# PSU.net
KiCad netlist of a schematic drawn in Altium Designer
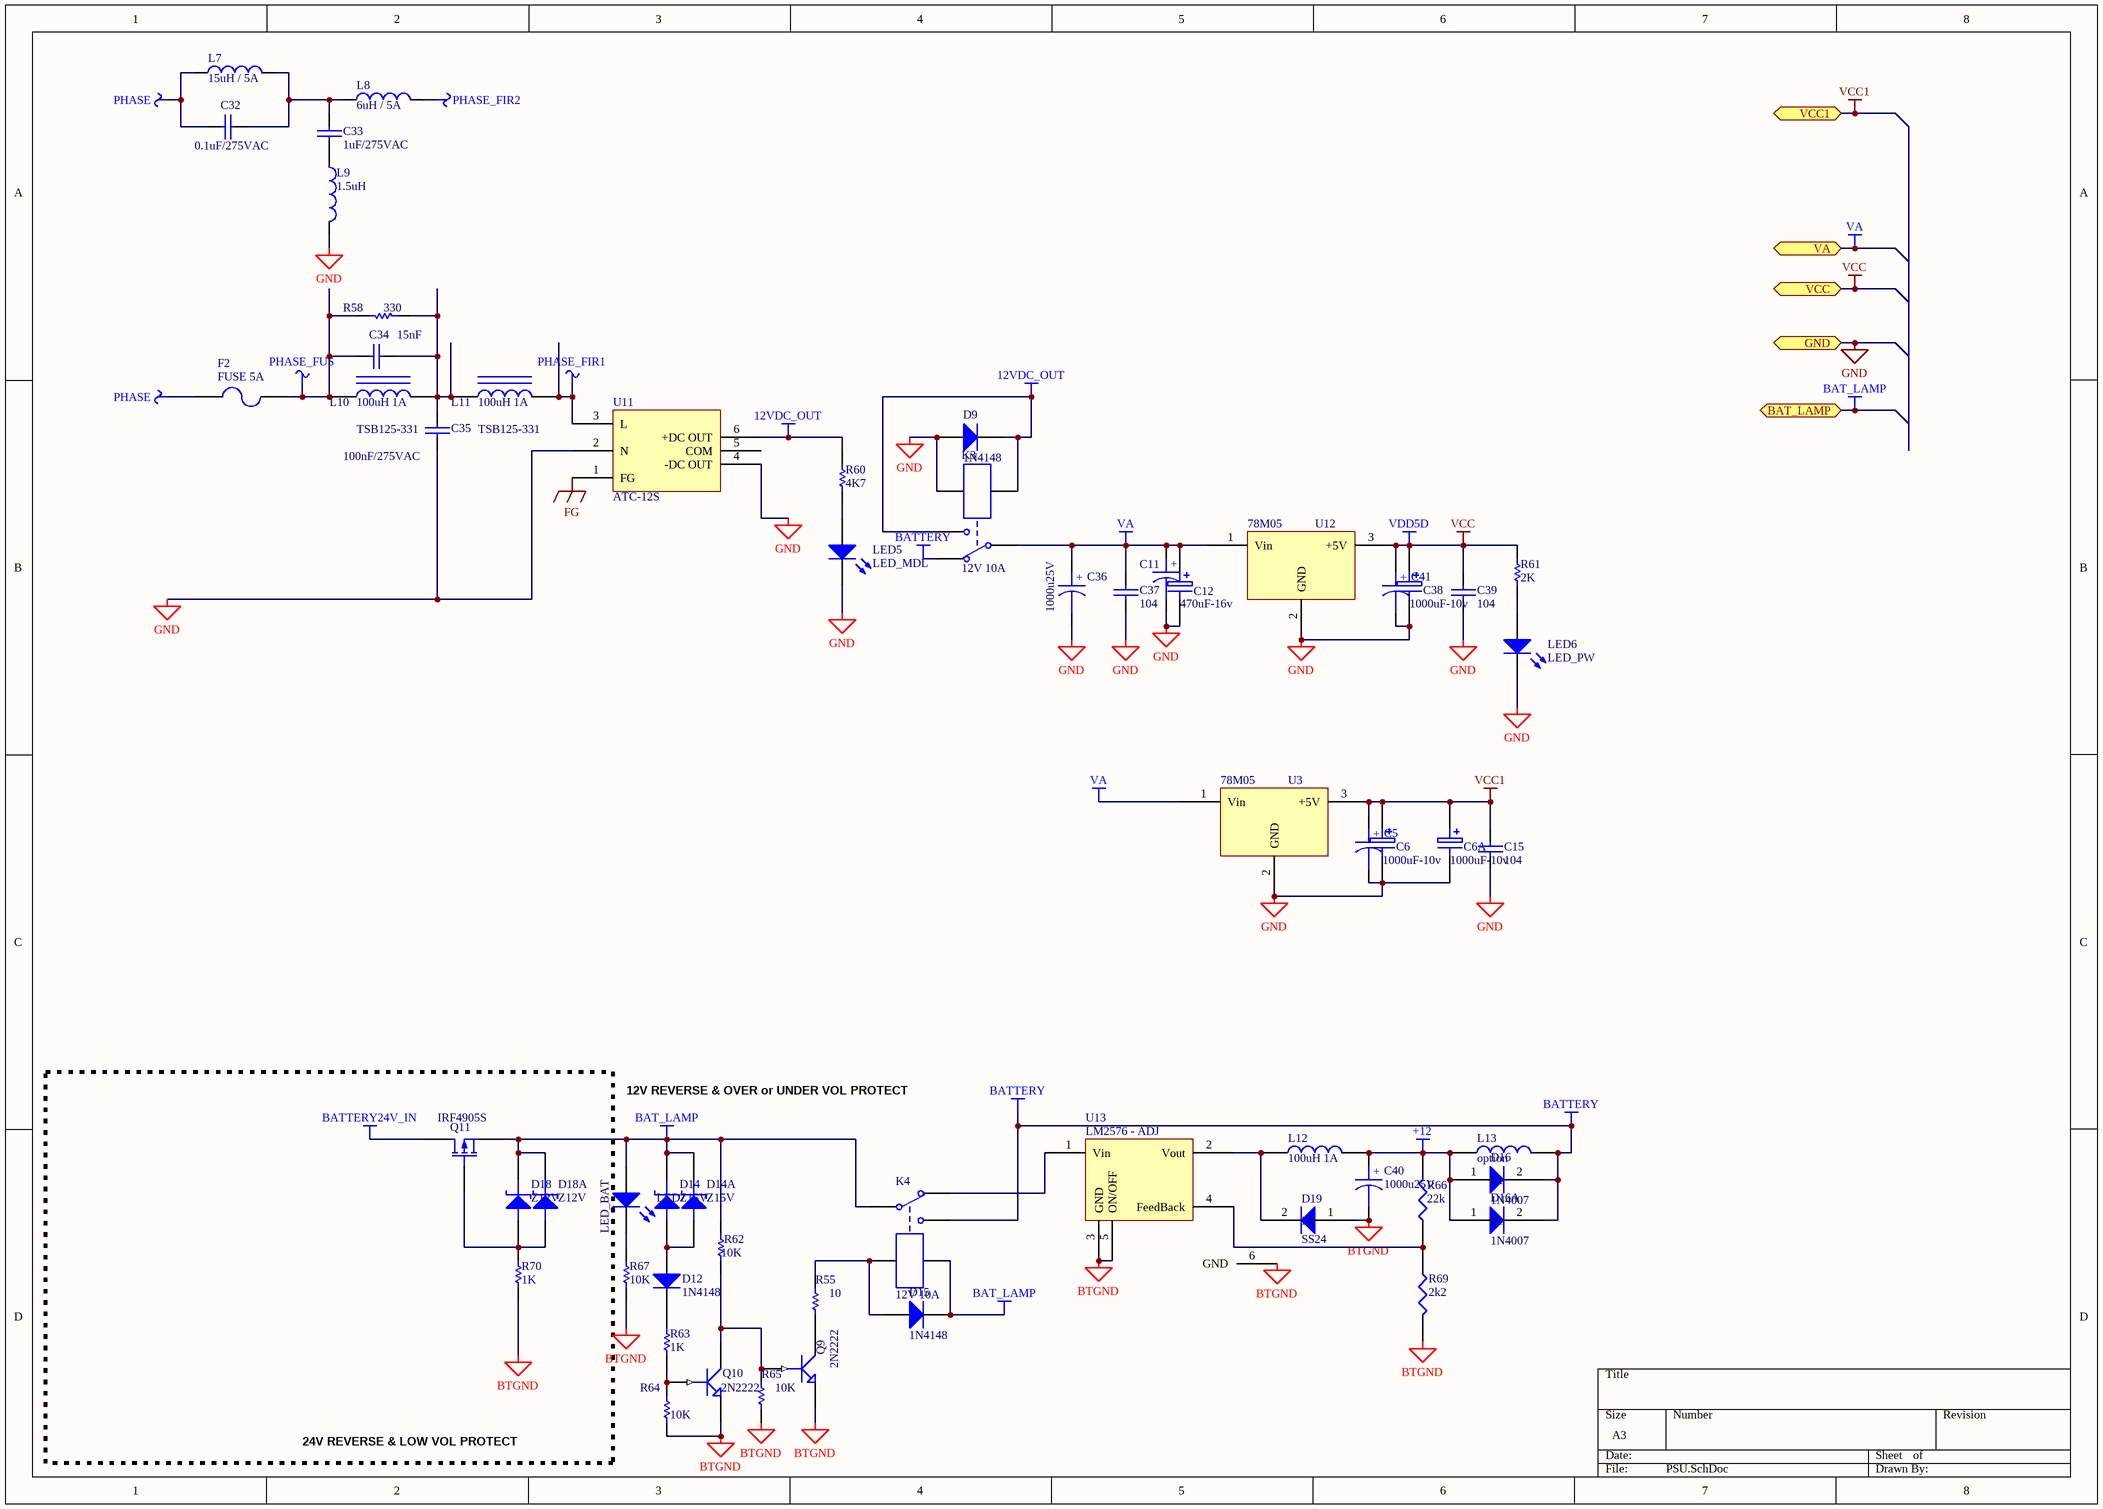
[diagram p0: PSU.SchDoc]

(export (version "E")
  (design (tool "Eeschema 10.0.6"))
  (components
    (comp (ref "C5")
      (value "1000u25V")
      (footprint "CAP40x20")
      (description "Capacitor")
      (libsource (lib "*") (part "CAPACITOR POL"))
    )
    (comp (ref "C6")
      (value "1000uF-10v")
      (footprint "CAP_ELEC_SIZE_E")
      (description "Electrolytic Capacitor")
      (libsource (lib "*") (part "ELECTRO1"))
    )
    (comp (ref "C6A")
      (value "1000uF-10v")
      (footprint "CAP_ELEC_SIZE_E")
      (description "Electrolytic Capacitor")
      (libsource (lib "*") (part "ELECTRO1"))
    )
    (comp (ref "C11")
      (value "1000u25V")
      (footprint "CAP40x20")
      (description "Capacitor")
      (libsource (lib "*") (part "CAPACITOR POL"))
    )
    (comp (ref "C12")
      (value "470uF-16v")
      (footprint "CAP_ELEC_SIZE_E")
      (description "Electrolytic Capacitor")
      (libsource (lib "*") (part "ELECTRO1"))
    )
    (comp (ref "C15")
      (value "104")
      (footprint "C6-0805_N")
      (description "Capacitor")
      (libsource (lib "*") (part "CAP"))
    )
    (comp (ref "C32")
      (value "0.1uF/275VAC")
      (footprint "100n400v")
      (description "0.1uF/275VAC X2")
      (libsource (lib "*") (part "CAP"))
    )
    (comp (ref "C33")
      (value "1uF/275VAC")
      (footprint "CAP1.2/0.5")
      (description "1uF/275VAC X2")
      (libsource (lib "*") (part "CAP"))
    )
    (comp (ref "C34")
      (value "15nF")
      (footprint "R3216[1206]")
      (description "Capacitor")
      (libsource (lib "*") (part "CAP"))
    )
    (comp (ref "C35")
      (value "100nF/275VAC")
      (footprint "100n400v")
      (description "100nF/275VAC X2")
      (libsource (lib "*") (part "CAP"))
    )
    (comp (ref "C36")
      (value "1000u25V")
      (footprint "CAP40x20")
      (description "Capacitor")
      (libsource (lib "*") (part "CAPACITOR POL"))
    )
    (comp (ref "C37")
      (value "104")
      (footprint "C6-0805_N")
      (description "Capacitor")
      (libsource (lib "*") (part "CAP"))
    )
    (comp (ref "C38")
      (value "1000uF-10v")
      (footprint "CAP_ELEC_SIZE_E")
      (description "Electrolytic Capacitor")
      (libsource (lib "*") (part "ELECTRO1"))
    )
    (comp (ref "C39")
      (value "104")
      (footprint "C6-0805_N")
      (description "Capacitor")
      (libsource (lib "*") (part "CAP"))
    )
    (comp (ref "C40")
      (value "1000u25V")
      (footprint "CAP40x20")
      (description "Capacitor")
      (libsource (lib "*") (part "CAPACITOR POL"))
    )
    (comp (ref "C41")
      (value "1000u25V")
      (footprint "CAP40x20")
      (description "Capacitor")
      (libsource (lib "*") (part "CAPACITOR POL"))
    )
    (comp (ref "D9")
      (value "1N4148")
      (footprint "SOD80, LL-34")
      (description "1 Amp General Purpose Rectifier")
      (fields (field (name "PUBLISHER") "Altium Limited"))
      (libsource (lib "*") (part "Diode 1N4007"))
    )
    (comp (ref "D12")
      (value "1N4148")
      (footprint "SOD80, LL-34")
      (description "1 Amp General Purpose Rectifier")
      (fields (field (name "PUBLISHER") "Altium Limited"))
      (libsource (lib "*") (part "Diode 1N4007"))
    )
    (comp (ref "D14")
      (value "Z15V")
      (footprint "DO-35")
      (description "Zener Diode")
      (libsource (lib "*") (part "ZENER2"))
    )
    (comp (ref "D14A")
      (value "Z15V")
      (footprint "SOT23-3")
      (description "Zener Diode")
      (libsource (lib "*") (part "ZENER2"))
    )
    (comp (ref "D15")
      (value "1N4148")
      (footprint "SOD80, LL-34")
      (description "1 Amp General Purpose Rectifier")
      (fields (field (name "PUBLISHER") "Altium Limited"))
      (libsource (lib "*") (part "Diode 1N4007"))
    )
    (comp (ref "D16")
      (value "1N4007")
      (footprint "DO-214AA")
      (description "Hoangphat")
      (libsource (lib "*") (part "DIODE"))
    )
    (comp (ref "D16A")
      (value "1N4007")
      (footprint "DO-214AA")
      (description "Hoangphat")
      (libsource (lib "*") (part "DIODE"))
    )
    (comp (ref "D18")
      (value "Z12V")
      (footprint "DO-35")
      (description "Zener Diode")
      (libsource (lib "*") (part "ZENER2"))
    )
    (comp (ref "D18A")
      (value "Z12V")
      (footprint "SOD80, LL-34")
      (description "Zener Diode")
      (libsource (lib "*") (part "ZENER2"))
    )
    (comp (ref "D19")
      (value "SS24")
      (footprint "DO-214AA")
      (description "Hoangphat")
      (libsource (lib "*") (part "DIODE"))
    )
    (comp (ref "F2")
      (value "FUSE 5A")
      (footprint "FUSE2")
      (description "Fuse")
      (libsource (lib "*") (part "FUSE2"))
    )
    (comp (ref "K3")
      (value "12V 10A")
      (footprint "RELAYVUONG")
      (description "G5LA-10A/250VAC / SRC-12VDC-SL-C")
      (fields (field (name "PUBLISHER") "Altium Limited"))
      (libsource (lib "Miscellaneous Devices") (part "Relay-SPDT"))
    )
    (comp (ref "K4")
      (value "12V 10A")
      (footprint "RELAYVUONG")
      (description "G5LA-10A/250VAC / SRC-12VDC-SL-C")
      (fields (field (name "PUBLISHER") "Altium Limited"))
      (libsource (lib "Miscellaneous Devices") (part "Relay-SPDT"))
    )
    (comp (ref "L7")
      (value "15uH / 5A")
      (footprint "IND26x8")
      (description "Toirodal Inductor")
      (fields (field (name "PUBLISHER") "Altium Limited"))
      (libsource (lib "Miscellaneous Devices") (part "Inductor"))
    )
    (comp (ref "L8")
      (value "6uH / 5A")
      (footprint "IND15X7")
      (description "Toirodal Inductor")
      (fields (field (name "PUBLISHER") "Altium Limited"))
      (libsource (lib "Miscellaneous Devices") (part "Inductor"))
    )
    (comp (ref "L9")
      (value "1.5uH")
      (footprint "IND15x7")
      (description "Toirodal Inductor")
      (fields (field (name "PUBLISHER") "Altium Limited"))
      (libsource (lib "Miscellaneous Devices") (part "Inductor"))
    )
    (comp (ref "L10")
      (value "100uH 1A")
      (footprint "IND1207")
      (description "100uH 1A SMD HP")
      (fields (field (name "ALTIUM_VALUE") "TSB125-331"))
      (libsource (lib "*") (part "INDUCTOR IRON"))
    )
    (comp (ref "L11")
      (value "100uH 1A")
      (footprint "IND1207")
      (description "100uH 1A SMD HP")
      (fields (field (name "ALTIUM_VALUE") "TSB125-331"))
      (libsource (lib "*") (part "INDUCTOR IRON"))
    )
    (comp (ref "L12") (value "100uH 1A") (footprint "IND1207") (libsource (lib "*") (part "INDUCTOR")))
    (comp (ref "L13") (value "option") (footprint "axial-0.3") (libsource (lib "*") (part "INDUCTOR")))
    (comp (ref "LED5")
      (value "LED_MDL")
      (footprint "LED3mm")
      (description "Typical BLUE SiC LED")
      (fields (field (name "PUBLISHER") "Altium Limited"))
      (libsource (lib "Miscellaneous Devices") (part "LED3"))
    )
    (comp (ref "LED6")
      (value "LED_PW")
      (footprint "LED3mm")
      (description "Typical BLUE SiC LED")
      (fields (field (name "PUBLISHER") "Altium Limited"))
      (libsource (lib "Miscellaneous Devices") (part "LED3"))
    )
    (comp (ref "LED7")
      (value "LED_BAT")
      (footprint "LED3mm")
      (description "Typical BLUE SiC LED")
      (fields (field (name "PUBLISHER") "Altium Limited"))
      (libsource (lib "Miscellaneous Devices") (part "LED3"))
    )
    (comp (ref "Q9")
      (value "2N2222")
      (footprint "SOT23-3")
      (description "NPN Transistor")
      (libsource (lib "*") (part "NPN1"))
    )
    (comp (ref "Q10")
      (value "2N2222")
      (footprint "SOT23-3")
      (description "NPN Transistor")
      (libsource (lib "*") (part "NPN1"))
    )
    (comp (ref "Q11")
      (value "IRF4905S")
      (footprint "D2PAK-3")
      (description "HEXFET Power P MOSFET")
      (fields (field (name "PUBLISHER") "Altium Limited"))
      (libsource (lib "Miscellaneous Devices") (part "MOSFET-P"))
    )
    (comp (ref "R55")
      (value "10")
      (footprint "6-0805_N")
      (description "Semiconductor Resistor")
      (fields (field (name "PUBLISHER") "*"))
      (libsource (lib "*") (part "Res Semi"))
    )
    (comp (ref "R58")
      (value "330")
      (footprint "R3216[1206]")
      (description "Semiconductor Resistor")
      (fields (field (name "PUBLISHER") "Altium Limited"))
      (libsource (lib "*") (part "Res Semi"))
    )
    (comp (ref "R60")
      (value "4K7")
      (footprint "6-0805_N")
      (description "Semiconductor Resistor")
      (fields (field (name "PUBLISHER") "*"))
      (libsource (lib "*") (part "Res Semi"))
    )
    (comp (ref "R61")
      (value "2K")
      (footprint "6-0805_N")
      (description "Semiconductor Resistor")
      (fields (field (name "PUBLISHER") "*"))
      (libsource (lib "*") (part "Res Semi"))
    )
    (comp (ref "R62")
      (value "10K")
      (footprint "6-0805_N")
      (description "Semiconductor Resistor")
      (fields (field (name "PUBLISHER") "*"))
      (libsource (lib "*") (part "Res Semi"))
    )
    (comp (ref "R63")
      (value "1K")
      (footprint "6-0805_N")
      (description "Semiconductor Resistor")
      (fields (field (name "PUBLISHER") "*"))
      (libsource (lib "*") (part "Res Semi"))
    )
    (comp (ref "R64")
      (value "10K")
      (footprint "6-0805_N")
      (description "Semiconductor Resistor")
      (fields (field (name "PUBLISHER") "*"))
      (libsource (lib "*") (part "Res Semi"))
    )
    (comp (ref "R65")
      (value "10K")
      (footprint "6-0805_N")
      (description "Semiconductor Resistor")
      (fields (field (name "PUBLISHER") "*"))
      (libsource (lib "*") (part "Res Semi"))
    )
    (comp (ref "R66") (value "22k") (footprint "6-0805_N") (libsource (lib "*") (part "RES1")))
    (comp (ref "R67")
      (value "10K")
      (footprint "6-0805_N")
      (description "Semiconductor Resistor")
      (fields (field (name "PUBLISHER") "*"))
      (libsource (lib "*") (part "Res Semi"))
    )
    (comp (ref "R69") (value "2k2") (footprint "6-0805_N") (libsource (lib "*") (part "RES1")))
    (comp (ref "R70")
      (value "1K")
      (footprint "6-0805_N")
      (description "Semiconductor Resistor")
      (fields (field (name "PUBLISHER") "*"))
      (libsource (lib "*") (part "Res Semi"))
    )
    (comp (ref "U3") (value "78M05") (footprint "D2PAK-3") (libsource (lib "*") (part "MC7805T")))
    (comp (ref "U11")
      (value "ATC-12S")
      (footprint "ATC MODULE")
      (libsource (lib "Schlib1") (part "Component_1"))
    )
    (comp (ref "U12") (value "78M05") (footprint "D2PAK-3") (libsource (lib "*") (part "MC7805T")))
    (comp (ref "U13") (value "LM2576 - ADJ") (footprint "TO-263-5") (libsource (lib "*") (part "LM2576")))
  )
  (nets
    (net (code "1") (name "+12") (class "Default")
      (node (ref "C40") (pin "1") (pinfunction "1_1") (pintype "passive"))
      (node (ref "D16") (pin "1") (pinfunction "1_1") (pintype "passive"))
      (node (ref "D16A") (pin "1") (pinfunction "1_1") (pintype "passive"))
      (node (ref "L12") (pin "2") (pinfunction "2_2") (pintype "passive"))
      (node (ref "L13") (pin "1") (pinfunction "1_1") (pintype "passive"))
      (node (ref "R66") (pin "2") (pinfunction "2_2") (pintype "passive"))
    )
    (net (code "2") (name "12VDC_OUT") (class "Default")
      (node (ref "D9") (pin "2") (pinfunction "K_2") (pintype "passive"))
      (node (ref "K3") (pin "3") (pinfunction "3_3") (pintype "passive"))
      (node (ref "K3") (pin "4") (pinfunction "4_4") (pintype "passive"))
      (node (ref "R60") (pin "2") (pinfunction "2_2") (pintype "passive"))
      (node (ref "U11") (pin "6") (pinfunction "+DC_OUT_6") (pintype "passive"))
    )
    (net (code "3") (name "BATTERY") (class "Default")
      (node (ref "D16") (pin "2") (pinfunction "2_2") (pintype "passive"))
      (node (ref "D16A") (pin "2") (pinfunction "2_2") (pintype "passive"))
      (node (ref "K3") (pin "2") (pinfunction "2_2") (pintype "passive"))
      (node (ref "K4") (pin "3") (pinfunction "3_3") (pintype "passive"))
      (node (ref "L13") (pin "2") (pinfunction "2_2") (pintype "passive"))
    )
    (net (code "4") (name "BATTERY24V_IN") (class "Default")
      (node (ref "Q11") (pin "2") (pinfunction "D_2") (pintype "passive"))
    )
    (net (code "5") (name "BAT_LAMP") (class "Default")
      (node (ref "D14") (pin "2") (pinfunction "K_2") (pintype "passive"))
      (node (ref "D14A") (pin "2") (pinfunction "K_2") (pintype "passive"))
      (node (ref "D15") (pin "2") (pinfunction "K_2") (pintype "passive"))
      (node (ref "D18") (pin "2") (pinfunction "K_2") (pintype "passive"))
      (node (ref "D18A") (pin "2") (pinfunction "K_2") (pintype "passive"))
      (node (ref "K4") (pin "1") (pinfunction "1_1") (pintype "passive"))
      (node (ref "K4") (pin "5") (pinfunction "5_5") (pintype "passive"))
      (node (ref "LED7") (pin "1") (pinfunction "A_1") (pintype "passive"))
      (node (ref "Q11") (pin "3") (pinfunction "S_3") (pintype "passive"))
      (node (ref "R62") (pin "2") (pinfunction "2_2") (pintype "passive"))
    )
    (net (code "6") (name "BTGND") (class "Default")
      (node (ref "C40") (pin "2") (pinfunction "2_2") (pintype "passive"))
      (node (ref "D19") (pin "1") (pinfunction "1_1") (pintype "passive"))
      (node (ref "Q10") (pin "2") (pinfunction "E_2") (pintype "passive"))
      (node (ref "Q9") (pin "2") (pinfunction "E_2") (pintype "passive"))
      (node (ref "R64") (pin "1") (pinfunction "1_1") (pintype "passive"))
      (node (ref "R65") (pin "1") (pinfunction "1_1") (pintype "passive"))
      (node (ref "R67") (pin "1") (pinfunction "1_1") (pintype "passive"))
      (node (ref "R69") (pin "2") (pinfunction "2_2") (pintype "passive"))
      (node (ref "R70") (pin "1") (pinfunction "1_1") (pintype "passive"))
      (node (ref "U13") (pin "3") (pinfunction "GND_3") (pintype "passive"))
      (node (ref "U13") (pin "5") (pinfunction "ON/OFF_5") (pintype "passive"))
      (node (ref "U13") (pin "6") (pinfunction "GND_6") (pintype "passive"))
    )
    (net (code "7") (name "FG") (class "Default")
      (node (ref "U11") (pin "1") (pinfunction "FG_1") (pintype "passive"))
    )
    (net (code "8") (name "GND") (class "Default")
      (node (ref "C11") (pin "2") (pinfunction "2_2") (pintype "passive"))
      (node (ref "C12") (pin "2") (pinfunction "2_2") (pintype "passive"))
      (node (ref "C15") (pin "2") (pinfunction "2_2") (pintype "passive"))
      (node (ref "C35") (pin "1") (pinfunction "1_1") (pintype "passive"))
      (node (ref "C36") (pin "2") (pinfunction "2_2") (pintype "passive"))
      (node (ref "C37") (pin "2") (pinfunction "2_2") (pintype "passive"))
      (node (ref "C38") (pin "2") (pinfunction "2_2") (pintype "passive"))
      (node (ref "C39") (pin "2") (pinfunction "2_2") (pintype "passive"))
      (node (ref "C41") (pin "2") (pinfunction "2_2") (pintype "passive"))
      (node (ref "C5") (pin "2") (pinfunction "2_2") (pintype "passive"))
      (node (ref "C6") (pin "2") (pinfunction "2_2") (pintype "passive"))
      (node (ref "C6A") (pin "2") (pinfunction "2_2") (pintype "passive"))
      (node (ref "D9") (pin "1") (pinfunction "A_1") (pintype "passive"))
      (node (ref "K3") (pin "5") (pinfunction "5_5") (pintype "passive"))
      (node (ref "L9") (pin "2") (pinfunction "2_2") (pintype "passive"))
      (node (ref "LED5") (pin "2") (pinfunction "K_2") (pintype "passive"))
      (node (ref "LED6") (pin "2") (pinfunction "K_2") (pintype "passive"))
      (node (ref "U11") (pin "2") (pinfunction "N_2") (pintype "passive"))
      (node (ref "U11") (pin "4") (pinfunction "-DC_OUT_4") (pintype "passive"))
      (node (ref "U12") (pin "2") (pinfunction "GND_2") (pintype "passive"))
      (node (ref "U3") (pin "2") (pinfunction "GND_2") (pintype "passive"))
    )
    (net (code "9") (name "Net-(C32-Pad1)") (class "Default")
      (node (ref "C32") (pin "1") (pinfunction "1_1") (pintype "passive"))
      (node (ref "C33") (pin "1") (pinfunction "1_1") (pintype "passive"))
      (node (ref "L7") (pin "2") (pinfunction "2_2") (pintype "passive"))
      (node (ref "L8") (pin "1") (pinfunction "1_1") (pintype "passive"))
    )
    (net (code "10") (name "Net-(C33-Pad2)") (class "Default")
      (node (ref "C33") (pin "2") (pinfunction "2_2") (pintype "passive"))
      (node (ref "L9") (pin "1") (pinfunction "1_1") (pintype "passive"))
    )
    (net (code "11") (name "Net-(C34-Pad2)") (class "Default")
      (node (ref "C34") (pin "2") (pinfunction "2_2") (pintype "passive"))
      (node (ref "C35") (pin "2") (pinfunction "2_2") (pintype "passive"))
      (node (ref "L10") (pin "2") (pinfunction "2_2") (pintype "passive"))
      (node (ref "L11") (pin "1") (pinfunction "1_1") (pintype "passive"))
      (node (ref "R58") (pin "1") (pinfunction "1_1") (pintype "passive"))
    )
    (net (code "12") (name "Net-(D12-A)") (class "Default")
      (node (ref "D12") (pin "1") (pinfunction "A_1") (pintype "passive"))
      (node (ref "D14") (pin "1") (pinfunction "A_1") (pintype "passive"))
      (node (ref "D14A") (pin "1") (pinfunction "A_1") (pintype "passive"))
    )
    (net (code "13") (name "Net-(D12-K)") (class "Default")
      (node (ref "D12") (pin "2") (pinfunction "K_2") (pintype "passive"))
      (node (ref "R63") (pin "2") (pinfunction "2_2") (pintype "passive"))
    )
    (net (code "14") (name "Net-(D15-A)") (class "Default")
      (node (ref "D15") (pin "1") (pinfunction "A_1") (pintype "passive"))
      (node (ref "K4") (pin "4") (pinfunction "4_4") (pintype "passive"))
      (node (ref "R55") (pin "2") (pinfunction "2_2") (pintype "passive"))
    )
    (net (code "15") (name "Net-(D18-A)") (class "Default")
      (node (ref "D18") (pin "1") (pinfunction "A_1") (pintype "passive"))
      (node (ref "D18A") (pin "1") (pinfunction "A_1") (pintype "passive"))
      (node (ref "Q11") (pin "1") (pinfunction "G_1") (pintype "passive"))
      (node (ref "R70") (pin "2") (pinfunction "2_2") (pintype "passive"))
    )
    (net (code "16") (name "Net-(LED5-A)") (class "Default")
      (node (ref "LED5") (pin "1") (pinfunction "A_1") (pintype "passive"))
      (node (ref "R60") (pin "1") (pinfunction "1_1") (pintype "passive"))
    )
    (net (code "17") (name "Net-(LED6-A)") (class "Default")
      (node (ref "LED6") (pin "1") (pinfunction "A_1") (pintype "passive"))
      (node (ref "R61") (pin "1") (pinfunction "1_1") (pintype "passive"))
    )
    (net (code "18") (name "Net-(LED7-K)") (class "Default")
      (node (ref "LED7") (pin "2") (pinfunction "K_2") (pintype "passive"))
      (node (ref "R67") (pin "2") (pinfunction "2_2") (pintype "passive"))
    )
    (net (code "19") (name "Net-(Q9-C)") (class "Default")
      (node (ref "Q9") (pin "3") (pinfunction "C_3") (pintype "passive"))
      (node (ref "R55") (pin "1") (pinfunction "1_1") (pintype "passive"))
    )
    (net (code "20") (name "Net-(Q10-B)") (class "Default")
      (node (ref "Q10") (pin "1") (pinfunction "B_1") (pintype "input"))
      (node (ref "R63") (pin "1") (pinfunction "1_1") (pintype "passive"))
      (node (ref "R64") (pin "2") (pinfunction "2_2") (pintype "passive"))
    )
    (net (code "21") (name "Net-(Q10-C)") (class "Default")
      (node (ref "Q10") (pin "3") (pinfunction "C_3") (pintype "passive"))
      (node (ref "Q9") (pin "1") (pinfunction "B_1") (pintype "input"))
      (node (ref "R62") (pin "1") (pinfunction "1_1") (pintype "passive"))
      (node (ref "R65") (pin "2") (pinfunction "2_2") (pintype "passive"))
    )
    (net (code "22") (name "Net-(U13-FeedBack)") (class "Default")
      (node (ref "R66") (pin "1") (pinfunction "1_1") (pintype "passive"))
      (node (ref "R69") (pin "1") (pinfunction "1_1") (pintype "passive"))
      (node (ref "U13") (pin "4") (pinfunction "FeedBack_4") (pintype "passive"))
    )
    (net (code "23") (name "Net-(U13-Vin)") (class "Default")
      (node (ref "K4") (pin "2") (pinfunction "2_2") (pintype "passive"))
      (node (ref "U13") (pin "1") (pinfunction "Vin_1") (pintype "passive"))
    )
    (net (code "24") (name "Net-(U13-Vout)") (class "Default")
      (node (ref "D19") (pin "2") (pinfunction "2_2") (pintype "passive"))
      (node (ref "L12") (pin "1") (pinfunction "1_1") (pintype "passive"))
      (node (ref "U13") (pin "2") (pinfunction "Vout_2") (pintype "passive"))
    )
    (net (code "25") (name "PHASE") (class "Default")
      (node (ref "C32") (pin "2") (pinfunction "2_2") (pintype "passive"))
      (node (ref "F2") (pin "1") (pinfunction "1_1") (pintype "passive"))
      (node (ref "L7") (pin "1") (pinfunction "1_1") (pintype "passive"))
    )
    (net (code "26") (name "PHASE_FIR1") (class "Default")
      (node (ref "L11") (pin "2") (pinfunction "2_2") (pintype "passive"))
      (node (ref "U11") (pin "3") (pinfunction "L_3") (pintype "passive"))
    )
    (net (code "27") (name "PHASE_FIR2") (class "Default")
      (node (ref "L8") (pin "2") (pinfunction "2_2") (pintype "passive"))
    )
    (net (code "28") (name "PHASE_FUS") (class "Default")
      (node (ref "C34") (pin "1") (pinfunction "1_1") (pintype "passive"))
      (node (ref "F2") (pin "2") (pinfunction "2_2") (pintype "passive"))
      (node (ref "L10") (pin "1") (pinfunction "1_1") (pintype "passive"))
      (node (ref "R58") (pin "2") (pinfunction "2_2") (pintype "passive"))
    )
    (net (code "29") (name "VA") (class "Default")
      (node (ref "C11") (pin "1") (pinfunction "1_1") (pintype "passive"))
      (node (ref "C12") (pin "1") (pinfunction "1_1") (pintype "passive"))
      (node (ref "C36") (pin "1") (pinfunction "1_1") (pintype "passive"))
      (node (ref "C37") (pin "1") (pinfunction "1_1") (pintype "passive"))
      (node (ref "K3") (pin "1") (pinfunction "1_1") (pintype "passive"))
      (node (ref "U12") (pin "1") (pinfunction "Vin_1") (pintype "passive"))
      (node (ref "U3") (pin "1") (pinfunction "Vin_1") (pintype "passive"))
    )
    (net (code "30") (name "VCC") (class "Default")
      (node (ref "C38") (pin "1") (pinfunction "1_1") (pintype "passive"))
      (node (ref "C39") (pin "1") (pinfunction "1_1") (pintype "passive"))
      (node (ref "C41") (pin "1") (pinfunction "1_1") (pintype "passive"))
      (node (ref "R61") (pin "2") (pinfunction "2_2") (pintype "passive"))
      (node (ref "U12") (pin "3") (pinfunction "+5V_3") (pintype "passive"))
    )
    (net (code "31") (name "VCC1") (class "Default")
      (node (ref "C15") (pin "1") (pinfunction "1_1") (pintype "passive"))
      (node (ref "C5") (pin "1") (pinfunction "1_1") (pintype "passive"))
      (node (ref "C6") (pin "1") (pinfunction "1_1") (pintype "passive"))
      (node (ref "C6A") (pin "1") (pinfunction "1_1") (pintype "passive"))
      (node (ref "U3") (pin "3") (pinfunction "+5V_3") (pintype "passive"))
    )
    (net (code "32") (name "unconnected-(U11-COM-Pad5)") (class "Default")
      (node (ref "U11") (pin "5") (pinfunction "COM_5") (pintype "passive"))
    )
  )
)
